# Power_Topology.net
KiCad netlist of a schematic drawn in Altium Designer
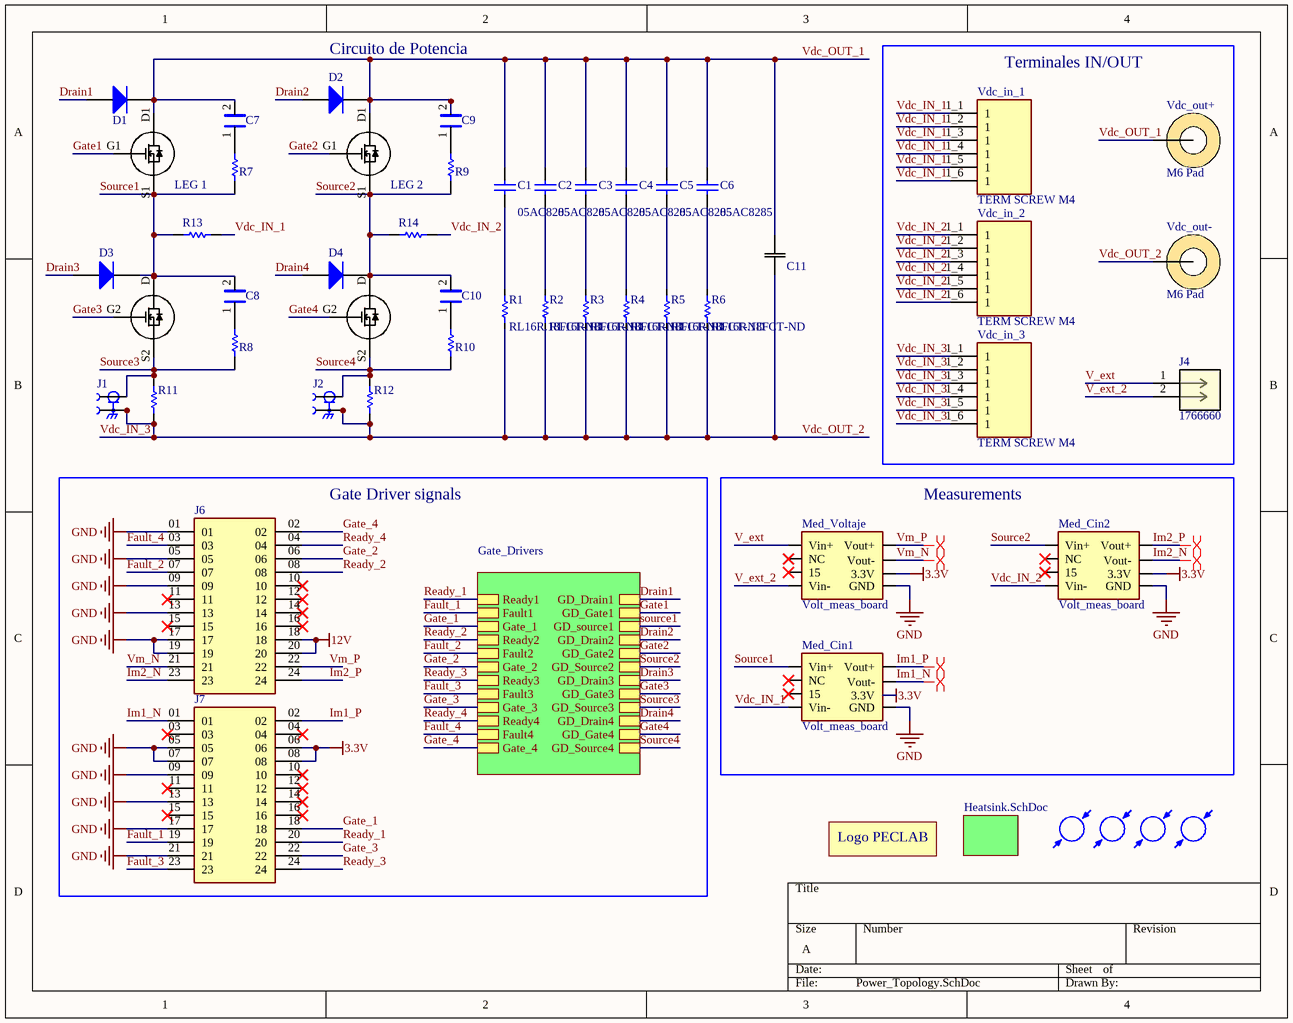
[diagram p0: Power_Topology.SchDoc]

(export (version "E")
  (design (tool "Eeschema 10.0.6"))
  (components
    (comp (ref "C1")
      (value "C1812C471JDGACTU")
      (footprint "CAP_1812")
      (description "Cap Ceramic 470pF 1000V C0G 5% SMD 1812 125°C Embossed Plastic T/R")
      (fields
        (field (name "MANUFACTURER") "KEMET")
        (field (name "TOLERANCE") "5%")
        (field (name "SUPPLIER PART NUMBER 1") "05AC8285")
      )
      (libsource (lib "H-Bridge 3-Leg - Lib") (part "C1812C471JDGACTU"))
    )
    (comp (ref "C2")
      (value "C1812C471JDGACTU")
      (footprint "CAP_1812")
      (description "Cap Ceramic 470pF 1000V C0G 5% SMD 1812 125°C Embossed Plastic T/R")
      (fields
        (field (name "MANUFACTURER") "KEMET")
        (field (name "TOLERANCE") "5%")
        (field (name "SUPPLIER PART NUMBER 1") "05AC8285")
      )
      (libsource (lib "H-Bridge 3-Leg - Lib") (part "C1812C471JDGACTU"))
    )
    (comp (ref "C3")
      (value "C1812C471JDGACTU")
      (footprint "CAP_1812")
      (description "Cap Ceramic 470pF 1000V C0G 5% SMD 1812 125°C Embossed Plastic T/R")
      (fields
        (field (name "MANUFACTURER") "KEMET")
        (field (name "TOLERANCE") "5%")
        (field (name "SUPPLIER PART NUMBER 1") "05AC8285")
      )
      (libsource (lib "H-Bridge 3-Leg - Lib") (part "C1812C471JDGACTU"))
    )
    (comp (ref "C4")
      (value "C1812C471JDGACTU")
      (footprint "CAP_1812")
      (description "Cap Ceramic 470pF 1000V C0G 5% SMD 1812 125°C Embossed Plastic T/R")
      (fields
        (field (name "MANUFACTURER") "KEMET")
        (field (name "TOLERANCE") "5%")
        (field (name "SUPPLIER PART NUMBER 1") "05AC8285")
      )
      (libsource (lib "H-Bridge 3-Leg - Lib") (part "C1812C471JDGACTU"))
    )
    (comp (ref "C5")
      (value "C1812C471JDGACTU")
      (footprint "CAP_1812")
      (description "Cap Ceramic 470pF 1000V C0G 5% SMD 1812 125°C Embossed Plastic T/R")
      (fields
        (field (name "MANUFACTURER") "KEMET")
        (field (name "TOLERANCE") "5%")
        (field (name "SUPPLIER PART NUMBER 1") "05AC8285")
      )
      (libsource (lib "H-Bridge 3-Leg - Lib") (part "C1812C471JDGACTU"))
    )
    (comp (ref "C6")
      (value "C1812C471JDGACTU")
      (footprint "CAP_1812")
      (description "Cap Ceramic 470pF 1000V C0G 5% SMD 1812 125°C Embossed Plastic T/R")
      (fields
        (field (name "MANUFACTURER") "KEMET")
        (field (name "TOLERANCE") "5%")
        (field (name "SUPPLIER PART NUMBER 1") "05AC8285")
      )
      (libsource (lib "H-Bridge 3-Leg - Lib") (part "C1812C471JDGACTU"))
    )
    (comp (ref "C7")
      (value "C1808C681JGGAC7800")
      (footprint "CAPC4520X200N")
      (description "CAP CER 680PF 2KV C0G/NP0 1808")
      (fields (field (name "MF") "KEMET"))
      (libsource (lib "H-Bridge 3-Leg - Lib") (part "CAP CER 680PF 1808"))
    )
    (comp (ref "C8")
      (value "C1808C681JGGAC7800")
      (footprint "CAPC4520X200N")
      (description "CAP CER 680PF 2KV C0G/NP0 1808")
      (fields (field (name "MF") "KEMET"))
      (libsource (lib "H-Bridge 3-Leg - Lib") (part "CAP CER 680PF 1808"))
    )
    (comp (ref "C9")
      (value "C1808C681JGGAC7800")
      (footprint "CAPC4520X200N")
      (description "CAP CER 680PF 2KV C0G/NP0 1808")
      (fields (field (name "MF") "KEMET"))
      (libsource (lib "H-Bridge 3-Leg - Lib") (part "CAP CER 680PF 1808"))
    )
    (comp (ref "C10")
      (value "C1808C681JGGAC7800")
      (footprint "CAPC4520X200N")
      (description "CAP CER 680PF 2KV C0G/NP0 1808")
      (fields (field (name "MF") "KEMET"))
      (libsource (lib "H-Bridge 3-Leg - Lib") (part "CAP CER 680PF 1808"))
    )
    (comp (ref "C11")
      (value "C4AQIBU5125A12J")
      (footprint "CAP_C4AQ_B_2_KEM")
      (description "12.5 µF Film Capacitor 800V Polypropylene (PP), Metallized Radial")
      (libsource (lib "H-Bridge 3-Leg - Lib") (part "Cap Film 12.5 uF"))
    )
    (comp (ref "D1")
      (value "ES1MTR")
      (footprint "SMA")
      (description "Diode Standard 1000 V 1A Surface Mount SMA")
      (fields (field (name "MF") "SMC Diode Solutions") (field (name "CREATED") "2021_05_16_EDuran"))
      (libsource (lib "H-Bridge 3-Leg - Lib") (part "Diode_1"))
    )
    (comp (ref "D2")
      (value "ES1MTR")
      (footprint "SMA")
      (description "Diode Standard 1000 V 1A Surface Mount SMA")
      (fields (field (name "MF") "SMC Diode Solutions") (field (name "CREATED") "2021_05_16_EDuran"))
      (libsource (lib "H-Bridge 3-Leg - Lib") (part "Diode_1"))
    )
    (comp (ref "D3")
      (value "ES1MTR")
      (footprint "SMA")
      (description "Diode Standard 1000 V 1A Surface Mount SMA")
      (fields (field (name "MF") "SMC Diode Solutions") (field (name "CREATED") "2021_05_16_EDuran"))
      (libsource (lib "H-Bridge 3-Leg - Lib") (part "Diode_1"))
    )
    (comp (ref "D4")
      (value "ES1MTR")
      (footprint "SMA")
      (description "Diode Standard 1000 V 1A Surface Mount SMA")
      (fields (field (name "MF") "SMC Diode Solutions") (field (name "CREATED") "2021_05_16_EDuran"))
      (libsource (lib "H-Bridge 3-Leg - Lib") (part "Diode_1"))
    )
    (comp (ref "J1")
      (value "CONUFL001-SMD-T")
      (footprint "LINX_CONUFL001-SMD-T")
      (description "U.FL (UMCC) Connector Jack, Male Pin 50Ohm Surface Mount Solder")
      (fields (field (name "MF") "Linx"))
      (libsource (lib "H-Bridge 3-Leg - Lib") (part "CONUFL001-SMD-T"))
    )
    (comp (ref "J2")
      (value "CONUFL001-SMD-T")
      (footprint "LINX_CONUFL001-SMD-T")
      (description "U.FL (UMCC) Connector Jack, Male Pin 50Ohm Surface Mount Solder")
      (fields (field (name "MF") "Linx"))
      (libsource (lib "H-Bridge 3-Leg - Lib") (part "CONUFL001-SMD-T"))
    )
    (comp (ref "J4")
      (value "1766660")
      (footprint "CONN_1766660")
      (description "No Description Available")
      (libsource (lib "H-Bridge 3-Leg - Lib") (part "1766660"))
    )
    (comp (ref "J6")
      (value "TSW-112-08-G-D-NA")
      (footprint "SAMTEC_TSW-112-08-G-D-NA")
      (description "Conn Unshrouded Header HDR 24 POS 2.54mm Solder RA Side Entry Thru-Hole Bulk")
      (fields (field (name "MF") "Samtec"))
      (libsource (lib "H-Bridge 3-Leg - Lib") (part "TSW-112-08-G-D-NA"))
    )
    (comp (ref "J7")
      (value "TSW-112-08-G-D-NA")
      (footprint "SAMTEC_TSW-112-08-G-D-NA")
      (description "Conn Unshrouded Header HDR 24 POS 2.54mm Solder RA Side Entry Thru-Hole Bulk")
      (fields (field (name "MF") "Samtec"))
      (libsource (lib "H-Bridge 3-Leg - Lib") (part "TSW-112-08-G-D-NA"))
    )
    (comp (ref "LEG 1")
      (value "MOSFET_SINK")
      (footprint "MOSFET-TO247_LEG_1")
      (libsource (lib "H-Bridge 3-Leg - Lib") (part "MOSFET_2_SINK_LEG_2"))
    )
    (comp (ref "LEG 2")
      (value "MOSFET_SINK")
      (footprint "MOSFET-TO247_LEG_2")
      (libsource (lib "H-Bridge 3-Leg - Lib") (part "MOSFET_2_SINK_LEG_2"))
    )
    (comp (ref "Logo")
      (value "LOGO PECLAB")
      (footprint "LOGO PECLAB 2")
      (libsource (lib "H-Bridge 3-Leg - Lib") (part "LOGO PECLAB"))
    )
    (comp (ref "Med_Cin1")
      (value "Volt_meas_board")
      (footprint "Volt_meas_board")
      (description "Tarjeta de medicion de voltaje con conector receptor 4 pos 2.54mm")
      (fields (field (name "MF") "Harwin Inc") (field (name "MP") "M20-7820446"))
      (libsource (lib "H-Bridge 3-Leg - Lib") (part "Volt_meas_board"))
    )
    (comp (ref "Med_Cin2")
      (value "Volt_meas_board")
      (footprint "Volt_meas_board")
      (description "Tarjeta de medicion de voltaje con conector receptor 4 pos 2.54mm")
      (fields (field (name "MF") "Harwin Inc") (field (name "MP") "M20-7820446"))
      (libsource (lib "H-Bridge 3-Leg - Lib") (part "Volt_meas_board"))
    )
    (comp (ref "Med_Voltaje")
      (value "Volt_meas_board")
      (footprint "Volt_meas_board")
      (description "Tarjeta de medicion de voltaje con conector receptor 4 pos 2.54mm")
      (fields (field (name "MF") "Harwin Inc") (field (name "MP") "M20-7820446"))
      (libsource (lib "H-Bridge 3-Leg - Lib") (part "Volt_meas_board"))
    )
    (comp (ref "MH1")
      (value "MH_3.4")
      (footprint "MH_3.4")
      (description "Non plated through hole")
      (libsource (lib "H-Bridge 3-Leg - Lib") (part "Mounting Hole"))
    )
    (comp (ref "MH2")
      (value "MH_3.4")
      (footprint "MH_3.4")
      (description "Non plated through hole")
      (libsource (lib "H-Bridge 3-Leg - Lib") (part "Mounting Hole"))
    )
    (comp (ref "MH3")
      (value "MH_3.4")
      (footprint "MH_3.4")
      (description "Non plated through hole")
      (libsource (lib "H-Bridge 3-Leg - Lib") (part "Mounting Hole"))
    )
    (comp (ref "MH4")
      (value "MH_3.4")
      (footprint "MH_3.4")
      (description "Non plated through hole")
      (libsource (lib "H-Bridge 3-Leg - Lib") (part "Mounting Hole"))
    )
    (comp (ref "R1")
      (value "RL1632R-R180-F")
      (footprint "R_1206")
      (description "Res Thin Film 1206 0.18 Ohm 1% 0.5W(1/2W) 0ppm/C to 100ppm/C Molded SMD Automotive T/R")
      (fields
        (field (name "MANUFACTURER") "Susumu")
        (field (name "TOLERANCE") "1%")
        (field (name "SUPPLIER PART NUMBER 1") "RL16R.18FCT-ND")
      )
      (libsource (lib "H-Bridge 3-Leg - Lib") (part "RL1632R-R180-F"))
    )
    (comp (ref "R2")
      (value "RL1632R-R180-F")
      (footprint "R_1206")
      (description "Res Thin Film 1206 0.18 Ohm 1% 0.5W(1/2W) 0ppm/C to 100ppm/C Molded SMD Automotive T/R")
      (fields
        (field (name "MANUFACTURER") "Susumu")
        (field (name "TOLERANCE") "1%")
        (field (name "SUPPLIER PART NUMBER 1") "RL16R.18FCT-ND")
      )
      (libsource (lib "H-Bridge 3-Leg - Lib") (part "RL1632R-R180-F"))
    )
    (comp (ref "R3")
      (value "RL1632R-R180-F")
      (footprint "R_1206")
      (description "Res Thin Film 1206 0.18 Ohm 1% 0.5W(1/2W) 0ppm/C to 100ppm/C Molded SMD Automotive T/R")
      (fields
        (field (name "MANUFACTURER") "Susumu")
        (field (name "TOLERANCE") "1%")
        (field (name "SUPPLIER PART NUMBER 1") "RL16R.18FCT-ND")
      )
      (libsource (lib "H-Bridge 3-Leg - Lib") (part "RL1632R-R180-F"))
    )
    (comp (ref "R4")
      (value "RL1632R-R180-F")
      (footprint "R_1206")
      (description "Res Thin Film 1206 0.18 Ohm 1% 0.5W(1/2W) 0ppm/C to 100ppm/C Molded SMD Automotive T/R")
      (fields
        (field (name "MANUFACTURER") "Susumu")
        (field (name "TOLERANCE") "1%")
        (field (name "SUPPLIER PART NUMBER 1") "RL16R.18FCT-ND")
      )
      (libsource (lib "H-Bridge 3-Leg - Lib") (part "RL1632R-R180-F"))
    )
    (comp (ref "R5")
      (value "RL1632R-R180-F")
      (footprint "R_1206")
      (description "Res Thin Film 1206 0.18 Ohm 1% 0.5W(1/2W) 0ppm/C to 100ppm/C Molded SMD Automotive T/R")
      (fields
        (field (name "MANUFACTURER") "Susumu")
        (field (name "TOLERANCE") "1%")
        (field (name "SUPPLIER PART NUMBER 1") "RL16R.18FCT-ND")
      )
      (libsource (lib "H-Bridge 3-Leg - Lib") (part "RL1632R-R180-F"))
    )
    (comp (ref "R6")
      (value "RL1632R-R180-F")
      (footprint "R_1206")
      (description "Res Thin Film 1206 0.18 Ohm 1% 0.5W(1/2W) 0ppm/C to 100ppm/C Molded SMD Automotive T/R")
      (fields
        (field (name "MANUFACTURER") "Susumu")
        (field (name "TOLERANCE") "1%")
        (field (name "SUPPLIER PART NUMBER 1") "RL16R.18FCT-ND")
      )
      (libsource (lib "H-Bridge 3-Leg - Lib") (part "RL1632R-R180-F"))
    )
    (comp (ref "R7")
      (value "Res 2010 4.7 Ohms")
      (footprint "RESC5025X70N")
      (fields (field (name "MF") "Vishay Dale") (field (name "MP") "CRCW20104R70JNEFHP"))
      (libsource (lib "H-Bridge 3-Leg - Lib") (part "Res 2010 4.7 Ohms"))
    )
    (comp (ref "R8")
      (value "Res 2010 4.7 Ohms")
      (footprint "RESC5025X70N")
      (fields (field (name "MF") "Vishay Dale") (field (name "MP") "CRCW20104R70JNEFHP"))
      (libsource (lib "H-Bridge 3-Leg - Lib") (part "Res 2010 4.7 Ohms"))
    )
    (comp (ref "R9")
      (value "Res 2010 4.7 Ohms")
      (footprint "RESC5025X70N")
      (fields (field (name "MF") "Vishay Dale") (field (name "MP") "CRCW20104R70JNEFHP"))
      (libsource (lib "H-Bridge 3-Leg - Lib") (part "Res 2010 4.7 Ohms"))
    )
    (comp (ref "R10")
      (value "Res 2010 4.7 Ohms")
      (footprint "RESC5025X70N")
      (fields (field (name "MF") "Vishay Dale") (field (name "MP") "CRCW20104R70JNEFHP"))
      (libsource (lib "H-Bridge 3-Leg - Lib") (part "Res 2010 4.7 Ohms"))
    )
    (comp (ref "R11")
      (value "WSHP2818R0100FEB")
      (footprint "RES_WSHP2818_VIS")
      (description "Current Sense Resistors - SMD 10watt .01ohm 1% AEC-Q200")
      (libsource (lib "H-Bridge 3-Leg - Lib") (part "WSHP2818R0100FEB"))
    )
    (comp (ref "R12")
      (value "WSHP2818R0100FEB")
      (footprint "RES_WSHP2818_VIS")
      (description "Current Sense Resistors - SMD 10watt .01ohm 1% AEC-Q200")
      (libsource (lib "H-Bridge 3-Leg - Lib") (part "WSHP2818R0100FEB"))
    )
    (comp (ref "R13")
      (value "WSHP2818R0100FEB")
      (footprint "RES_WSHP2818_VIS")
      (description "Current Sense Resistors - SMD 10watt .01ohm 1% AEC-Q200")
      (libsource (lib "H-Bridge 3-Leg - Lib") (part "WSHP2818R0100FEB"))
    )
    (comp (ref "R14")
      (value "WSHP2818R0100FEB")
      (footprint "RES_WSHP2818_VIS")
      (description "Current Sense Resistors - SMD 10watt .01ohm 1% AEC-Q200")
      (libsource (lib "H-Bridge 3-Leg - Lib") (part "WSHP2818R0100FEB"))
    )
    (comp (ref "Vdc_in_1")
      (value "TERM SCREW M4")
      (footprint "KEYSTONE_7799")
      (description "M4 Snap In PC Mount 30Amp-w Screw Unassembled")
      (fields (field (name "MF") "Keystone") (field (name "MP") "7799"))
      (libsource (lib "H-Bridge 3-Leg - Lib") (part "TERM SCREW M4"))
    )
    (comp (ref "Vdc_in_2")
      (value "TERM SCREW M4")
      (footprint "KEYSTONE_7799")
      (description "M4 Snap In PC Mount 30Amp-w Screw Unassembled")
      (fields (field (name "MF") "Keystone") (field (name "MP") "7799"))
      (libsource (lib "H-Bridge 3-Leg - Lib") (part "TERM SCREW M4"))
    )
    (comp (ref "Vdc_in_3")
      (value "TERM SCREW M4")
      (footprint "KEYSTONE_7799")
      (description "M4 Snap In PC Mount 30Amp-w Screw Unassembled")
      (fields (field (name "MF") "Keystone") (field (name "MP") "7799"))
      (libsource (lib "H-Bridge 3-Leg - Lib") (part "TERM SCREW M4"))
    )
    (comp (ref "Vdc_out+")
      (value "M6 Pad")
      (footprint "M6 PAD Connector")
      (description "Pad M6")
      (fields (field (name "CREATED") "2021_07_09_DArancibia"))
      (libsource (lib "H-Bridge 3-Leg - Lib") (part "Con_Pad_M6"))
    )
    (comp (ref "Vdc_out-")
      (value "M6 Pad")
      (footprint "M6 PAD Connector")
      (description "Pad M6")
      (fields (field (name "CREATED") "2021_07_09_DArancibia"))
      (libsource (lib "H-Bridge 3-Leg - Lib") (part "Con_Pad_M6"))
    )
  )
  (nets
    (net (code "1") (name "/Drain1") (class "Default")
      (node (ref "D1") (pin "A") (pinfunction "A_A") (pintype "passive"))
    )
    (net (code "2") (name "/Drain2") (class "Default")
      (node (ref "D2") (pin "A") (pinfunction "A_A") (pintype "passive"))
    )
    (net (code "3") (name "/Drain3") (class "Default")
      (node (ref "D3") (pin "A") (pinfunction "A_A") (pintype "passive"))
    )
    (net (code "4") (name "/Drain4") (class "Default")
      (node (ref "D4") (pin "A") (pinfunction "A_A") (pintype "passive"))
    )
    (net (code "5") (name "/Fault_1") (class "Default")
      (node (ref "J7") (pin "19") (pinfunction "19_19") (pintype "passive"))
    )
    (net (code "6") (name "/Fault_2") (class "Default")
      (node (ref "J6") (pin "07") (pinfunction "07_07") (pintype "passive"))
    )
    (net (code "7") (name "/Fault_3") (class "Default")
      (node (ref "J7") (pin "23") (pinfunction "23_23") (pintype "passive"))
    )
    (net (code "8") (name "/Fault_4") (class "Default")
      (node (ref "J6") (pin "03") (pinfunction "03_03") (pintype "passive"))
    )
    (net (code "9") (name "/Gate1") (class "Default")
      (node (ref "LEG 1") (pin "G1") (pinfunction "G1_G1") (pintype "passive"))
    )
    (net (code "10") (name "/Gate2") (class "Default")
      (node (ref "LEG 2") (pin "G1") (pinfunction "G1_G1") (pintype "passive"))
    )
    (net (code "11") (name "/Gate3") (class "Default")
      (node (ref "LEG 1") (pin "G2") (pinfunction "G2_G2") (pintype "passive"))
    )
    (net (code "12") (name "/Gate4") (class "Default")
      (node (ref "LEG 2") (pin "G2") (pinfunction "G2_G2") (pintype "passive"))
    )
    (net (code "13") (name "/Gate_1") (class "Default")
      (node (ref "J7") (pin "18") (pinfunction "18_18") (pintype "passive"))
    )
    (net (code "14") (name "/Gate_2") (class "Default")
      (node (ref "J6") (pin "06") (pinfunction "06_06") (pintype "passive"))
    )
    (net (code "15") (name "/Gate_3") (class "Default")
      (node (ref "J7") (pin "22") (pinfunction "22_22") (pintype "passive"))
    )
    (net (code "16") (name "/Gate_4") (class "Default")
      (node (ref "J6") (pin "02") (pinfunction "02_02") (pintype "passive"))
    )
    (net (code "17") (name "/Im1_N") (class "Default")
      (node (ref "J7") (pin "01") (pinfunction "01_01") (pintype "passive"))
      (node (ref "Med_Cin1") (pin "5") (pinfunction "Vout-_5") (pintype "passive"))
    )
    (net (code "18") (name "/Im1_P") (class "Default")
      (node (ref "J7") (pin "02") (pinfunction "02_02") (pintype "passive"))
      (node (ref "Med_Cin1") (pin "4") (pinfunction "Vout+_4") (pintype "passive"))
    )
    (net (code "19") (name "/Im2_N") (class "Default")
      (node (ref "J6") (pin "23") (pinfunction "23_23") (pintype "passive"))
      (node (ref "Med_Cin2") (pin "5") (pinfunction "Vout-_5") (pintype "passive"))
    )
    (net (code "20") (name "/Im2_P") (class "Default")
      (node (ref "J6") (pin "24") (pinfunction "24_24") (pintype "passive"))
      (node (ref "Med_Cin2") (pin "4") (pinfunction "Vout+_4") (pintype "passive"))
    )
    (net (code "21") (name "/Ready_1") (class "Default")
      (node (ref "J7") (pin "20") (pinfunction "20_20") (pintype "passive"))
    )
    (net (code "22") (name "/Ready_2") (class "Default")
      (node (ref "J6") (pin "08") (pinfunction "08_08") (pintype "passive"))
    )
    (net (code "23") (name "/Ready_3") (class "Default")
      (node (ref "J7") (pin "24") (pinfunction "24_24") (pintype "passive"))
    )
    (net (code "24") (name "/Ready_4") (class "Default")
      (node (ref "J6") (pin "04") (pinfunction "04_04") (pintype "passive"))
    )
    (net (code "25") (name "/Source1") (class "Default")
      (node (ref "C8") (pin "2") (pinfunction "2_2") (pintype "passive"))
      (node (ref "D3") (pin "K") (pinfunction "K_K") (pintype "passive"))
      (node (ref "LEG 1") (pin "D") (pinfunction "D_D") (pintype "passive"))
      (node (ref "LEG 1") (pin "S1") (pinfunction "S1_S1") (pintype "passive"))
      (node (ref "Med_Cin1") (pin "0") (pinfunction "Vin+_0") (pintype "passive"))
      (node (ref "R13") (pin "1") (pinfunction "1_1") (pintype "passive"))
      (node (ref "R7") (pin "1") (pinfunction "1_1") (pintype "passive"))
    )
    (net (code "26") (name "/Source2") (class "Default")
      (node (ref "C10") (pin "2") (pinfunction "2_2") (pintype "passive"))
      (node (ref "D4") (pin "K") (pinfunction "K_K") (pintype "passive"))
      (node (ref "LEG 2") (pin "D") (pinfunction "D_D") (pintype "passive"))
      (node (ref "LEG 2") (pin "S1") (pinfunction "S1_S1") (pintype "passive"))
      (node (ref "Med_Cin2") (pin "0") (pinfunction "Vin+_0") (pintype "passive"))
      (node (ref "R14") (pin "1") (pinfunction "1_1") (pintype "passive"))
      (node (ref "R9") (pin "1") (pinfunction "1_1") (pintype "passive"))
    )
    (net (code "27") (name "/Source3") (class "Default")
      (node (ref "J1") (pin "1") (pinfunction "1_1") (pintype "passive"))
      (node (ref "LEG 1") (pin "S2") (pinfunction "S2_S2") (pintype "passive"))
      (node (ref "R11") (pin "1") (pinfunction "1_1") (pintype "passive"))
      (node (ref "R8") (pin "1") (pinfunction "1_1") (pintype "passive"))
    )
    (net (code "28") (name "/Source4") (class "Default")
      (node (ref "J2") (pin "1") (pinfunction "1_1") (pintype "passive"))
      (node (ref "LEG 2") (pin "S2") (pinfunction "S2_S2") (pintype "passive"))
      (node (ref "R10") (pin "1") (pinfunction "1_1") (pintype "passive"))
      (node (ref "R12") (pin "1") (pinfunction "1_1") (pintype "passive"))
    )
    (net (code "29") (name "/V_ext") (class "Default")
      (node (ref "J4") (pin "1") (pinfunction "1_1") (pintype "passive"))
      (node (ref "Med_Voltaje") (pin "0") (pinfunction "Vin+_0") (pintype "passive"))
    )
    (net (code "30") (name "/V_ext_2") (class "Default")
      (node (ref "J4") (pin "2") (pinfunction "2_2") (pintype "passive"))
      (node (ref "Med_Voltaje") (pin "3") (pinfunction "Vin-_3") (pintype "passive"))
    )
    (net (code "31") (name "/Vdc_IN_1") (class "Default")
      (node (ref "Med_Cin1") (pin "3") (pinfunction "Vin-_3") (pintype "passive"))
      (node (ref "R13") (pin "2") (pinfunction "2_2") (pintype "passive"))
      (node (ref "Vdc_in_1") (pin "1_1") (pinfunction "1_1_1") (pintype "passive"))
      (node (ref "Vdc_in_1") (pin "1_2") (pinfunction "1_1_2") (pintype "passive"))
      (node (ref "Vdc_in_1") (pin "1_3") (pinfunction "1_1_3") (pintype "passive"))
      (node (ref "Vdc_in_1") (pin "1_4") (pinfunction "1_1_4") (pintype "passive"))
      (node (ref "Vdc_in_1") (pin "1_5") (pinfunction "1_1_5") (pintype "passive"))
      (node (ref "Vdc_in_1") (pin "1_6") (pinfunction "1_1_6") (pintype "passive"))
    )
    (net (code "32") (name "/Vdc_IN_2") (class "Default")
      (node (ref "Med_Cin2") (pin "3") (pinfunction "Vin-_3") (pintype "passive"))
      (node (ref "R14") (pin "2") (pinfunction "2_2") (pintype "passive"))
      (node (ref "Vdc_in_2") (pin "1_1") (pinfunction "1_1_1") (pintype "passive"))
      (node (ref "Vdc_in_2") (pin "1_2") (pinfunction "1_1_2") (pintype "passive"))
      (node (ref "Vdc_in_2") (pin "1_3") (pinfunction "1_1_3") (pintype "passive"))
      (node (ref "Vdc_in_2") (pin "1_4") (pinfunction "1_1_4") (pintype "passive"))
      (node (ref "Vdc_in_2") (pin "1_5") (pinfunction "1_1_5") (pintype "passive"))
      (node (ref "Vdc_in_2") (pin "1_6") (pinfunction "1_1_6") (pintype "passive"))
    )
    (net (code "33") (name "/Vdc_IN_3") (class "Default")
      (node (ref "C11") (pin "1") (pinfunction "1_1") (pintype "passive"))
      (node (ref "J1") (pin "2") (pinfunction "2_2") (pintype "passive"))
      (node (ref "J1") (pin "3") (pinfunction "2_3") (pintype "passive"))
      (node (ref "J2") (pin "2") (pinfunction "2_2") (pintype "passive"))
      (node (ref "J2") (pin "3") (pinfunction "2_3") (pintype "passive"))
      (node (ref "R1") (pin "1") (pinfunction "1_1") (pintype "passive"))
      (node (ref "R11") (pin "2") (pinfunction "2_2") (pintype "passive"))
      (node (ref "R12") (pin "2") (pinfunction "2_2") (pintype "passive"))
      (node (ref "R2") (pin "1") (pinfunction "1_1") (pintype "passive"))
      (node (ref "R3") (pin "1") (pinfunction "1_1") (pintype "passive"))
      (node (ref "R4") (pin "1") (pinfunction "1_1") (pintype "passive"))
      (node (ref "R5") (pin "1") (pinfunction "1_1") (pintype "passive"))
      (node (ref "R6") (pin "1") (pinfunction "1_1") (pintype "passive"))
      (node (ref "Vdc_in_3") (pin "1_1") (pinfunction "1_1_1") (pintype "passive"))
      (node (ref "Vdc_in_3") (pin "1_2") (pinfunction "1_1_2") (pintype "passive"))
      (node (ref "Vdc_in_3") (pin "1_3") (pinfunction "1_1_3") (pintype "passive"))
      (node (ref "Vdc_in_3") (pin "1_4") (pinfunction "1_1_4") (pintype "passive"))
      (node (ref "Vdc_in_3") (pin "1_5") (pinfunction "1_1_5") (pintype "passive"))
      (node (ref "Vdc_in_3") (pin "1_6") (pinfunction "1_1_6") (pintype "passive"))
      (node (ref "Vdc_out-") (pin "1") (pinfunction "1_1") (pintype "passive"))
    )
    (net (code "34") (name "/Vdc_OUT_1") (class "Default")
      (node (ref "C1") (pin "1") (pinfunction "1_1") (pintype "passive"))
      (node (ref "C11") (pin "2") (pinfunction "2_2") (pintype "passive"))
      (node (ref "C2") (pin "1") (pinfunction "1_1") (pintype "passive"))
      (node (ref "C3") (pin "1") (pinfunction "1_1") (pintype "passive"))
      (node (ref "C4") (pin "1") (pinfunction "1_1") (pintype "passive"))
      (node (ref "C5") (pin "1") (pinfunction "1_1") (pintype "passive"))
      (node (ref "C6") (pin "1") (pinfunction "1_1") (pintype "passive"))
      (node (ref "C7") (pin "2") (pinfunction "2_2") (pintype "passive"))
      (node (ref "C9") (pin "2") (pinfunction "2_2") (pintype "passive"))
      (node (ref "D1") (pin "K") (pinfunction "K_K") (pintype "passive"))
      (node (ref "D2") (pin "K") (pinfunction "K_K") (pintype "passive"))
      (node (ref "LEG 1") (pin "D1") (pinfunction "D1_D1") (pintype "passive"))
      (node (ref "LEG 2") (pin "D1") (pinfunction "D1_D1") (pintype "passive"))
      (node (ref "Vdc_out+") (pin "1") (pinfunction "1_1") (pintype "passive"))
    )
    (net (code "35") (name "/Vm_N") (class "Default")
      (node (ref "J6") (pin "21") (pinfunction "21_21") (pintype "passive"))
      (node (ref "Med_Voltaje") (pin "5") (pinfunction "Vout-_5") (pintype "passive"))
    )
    (net (code "36") (name "/Vm_P") (class "Default")
      (node (ref "J6") (pin "22") (pinfunction "22_22") (pintype "passive"))
      (node (ref "Med_Voltaje") (pin "4") (pinfunction "Vout+_4") (pintype "passive"))
    )
    (net (code "38") (name "3.3V") (class "Default")
      (node (ref "J7") (pin "06") (pinfunction "06_06") (pintype "passive"))
      (node (ref "J7") (pin "08") (pinfunction "08_08") (pintype "passive"))
      (node (ref "Med_Cin1") (pin "6") (pinfunction "3.3V_6") (pintype "passive"))
      (node (ref "Med_Cin2") (pin "6") (pinfunction "3.3V_6") (pintype "passive"))
      (node (ref "Med_Voltaje") (pin "6") (pinfunction "3.3V_6") (pintype "passive"))
    )
    (net (code "39") (name "12V") (class "Default")
      (node (ref "J6") (pin "18") (pinfunction "18_18") (pintype "passive"))
      (node (ref "J6") (pin "20") (pinfunction "20_20") (pintype "passive"))
    )
    (net (code "40") (name "GND") (class "Default")
      (node (ref "J6") (pin "01") (pinfunction "01_01") (pintype "passive"))
      (node (ref "J6") (pin "05") (pinfunction "05_05") (pintype "passive"))
      (node (ref "J6") (pin "09") (pinfunction "09_09") (pintype "passive"))
      (node (ref "J6") (pin "13") (pinfunction "13_13") (pintype "passive"))
      (node (ref "J6") (pin "17") (pinfunction "17_17") (pintype "passive"))
      (node (ref "J6") (pin "19") (pinfunction "19_19") (pintype "passive"))
      (node (ref "J7") (pin "05") (pinfunction "05_05") (pintype "passive"))
      (node (ref "J7") (pin "07") (pinfunction "07_07") (pintype "passive"))
      (node (ref "J7") (pin "09") (pinfunction "09_09") (pintype "passive"))
      (node (ref "J7") (pin "13") (pinfunction "13_13") (pintype "passive"))
      (node (ref "J7") (pin "17") (pinfunction "17_17") (pintype "passive"))
      (node (ref "J7") (pin "21") (pinfunction "21_21") (pintype "passive"))
      (node (ref "Med_Cin1") (pin "7") (pinfunction "GND_7") (pintype "passive"))
      (node (ref "Med_Cin2") (pin "7") (pinfunction "GND_7") (pintype "passive"))
      (node (ref "Med_Voltaje") (pin "7") (pinfunction "GND_7") (pintype "passive"))
    )
    (net (code "41") (name "Net-(C1-Pad2)") (class "Default")
      (node (ref "C1") (pin "2") (pinfunction "2_2") (pintype "passive"))
      (node (ref "R1") (pin "2") (pinfunction "2_2") (pintype "passive"))
    )
    (net (code "42") (name "Net-(C2-Pad2)") (class "Default")
      (node (ref "C2") (pin "2") (pinfunction "2_2") (pintype "passive"))
      (node (ref "R2") (pin "2") (pinfunction "2_2") (pintype "passive"))
    )
    (net (code "43") (name "Net-(C3-Pad2)") (class "Default")
      (node (ref "C3") (pin "2") (pinfunction "2_2") (pintype "passive"))
      (node (ref "R3") (pin "2") (pinfunction "2_2") (pintype "passive"))
    )
    (net (code "44") (name "Net-(C4-Pad2)") (class "Default")
      (node (ref "C4") (pin "2") (pinfunction "2_2") (pintype "passive"))
      (node (ref "R4") (pin "2") (pinfunction "2_2") (pintype "passive"))
    )
    (net (code "45") (name "Net-(C5-Pad2)") (class "Default")
      (node (ref "C5") (pin "2") (pinfunction "2_2") (pintype "passive"))
      (node (ref "R5") (pin "2") (pinfunction "2_2") (pintype "passive"))
    )
    (net (code "46") (name "Net-(C6-Pad2)") (class "Default")
      (node (ref "C6") (pin "2") (pinfunction "2_2") (pintype "passive"))
      (node (ref "R6") (pin "2") (pinfunction "2_2") (pintype "passive"))
    )
    (net (code "47") (name "Net-(C7-Pad1)") (class "Default")
      (node (ref "C7") (pin "1") (pinfunction "1_1") (pintype "passive"))
      (node (ref "R7") (pin "2") (pinfunction "2_2") (pintype "passive"))
    )
    (net (code "48") (name "Net-(C8-Pad1)") (class "Default")
      (node (ref "C8") (pin "1") (pinfunction "1_1") (pintype "passive"))
      (node (ref "R8") (pin "2") (pinfunction "2_2") (pintype "passive"))
    )
    (net (code "49") (name "Net-(C9-Pad1)") (class "Default")
      (node (ref "C9") (pin "1") (pinfunction "1_1") (pintype "passive"))
      (node (ref "R9") (pin "2") (pinfunction "2_2") (pintype "passive"))
    )
    (net (code "50") (name "Net-(C10-Pad1)") (class "Default")
      (node (ref "C10") (pin "1") (pinfunction "1_1") (pintype "passive"))
      (node (ref "R10") (pin "2") (pinfunction "2_2") (pintype "passive"))
    )
    (net (code "51") (name "unconnected-(J6-Pad10)") (class "Default")
      (node (ref "J6") (pin "10") (pinfunction "10_10") (pintype "passive+no_connect"))
    )
    (net (code "52") (name "unconnected-(J6-Pad11)") (class "Default")
      (node (ref "J6") (pin "11") (pinfunction "11_11") (pintype "passive+no_connect"))
    )
    (net (code "53") (name "unconnected-(J6-Pad12)") (class "Default")
      (node (ref "J6") (pin "12") (pinfunction "12_12") (pintype "passive+no_connect"))
    )
    (net (code "54") (name "unconnected-(J6-Pad14)") (class "Default")
      (node (ref "J6") (pin "14") (pinfunction "14_14") (pintype "passive+no_connect"))
    )
    (net (code "55") (name "unconnected-(J6-Pad15)") (class "Default")
      (node (ref "J6") (pin "15") (pinfunction "15_15") (pintype "passive+no_connect"))
    )
    (net (code "56") (name "unconnected-(J6-Pad16)") (class "Default")
      (node (ref "J6") (pin "16") (pinfunction "16_16") (pintype "passive+no_connect"))
    )
    (net (code "57") (name "unconnected-(J7-Pad03)") (class "Default")
      (node (ref "J7") (pin "03") (pinfunction "03_03") (pintype "passive+no_connect"))
    )
    (net (code "58") (name "unconnected-(J7-Pad04)") (class "Default")
      (node (ref "J7") (pin "04") (pinfunction "04_04") (pintype "passive+no_connect"))
    )
    (net (code "59") (name "unconnected-(J7-Pad10)") (class "Default")
      (node (ref "J7") (pin "10") (pinfunction "10_10") (pintype "passive+no_connect"))
    )
    (net (code "60") (name "unconnected-(J7-Pad11)") (class "Default")
      (node (ref "J7") (pin "11") (pinfunction "11_11") (pintype "passive+no_connect"))
    )
    (net (code "61") (name "unconnected-(J7-Pad12)") (class "Default")
      (node (ref "J7") (pin "12") (pinfunction "12_12") (pintype "passive+no_connect"))
    )
    (net (code "62") (name "unconnected-(J7-Pad14)") (class "Default")
      (node (ref "J7") (pin "14") (pinfunction "14_14") (pintype "passive+no_connect"))
    )
    (net (code "63") (name "unconnected-(J7-Pad15)") (class "Default")
      (node (ref "J7") (pin "15") (pinfunction "15_15") (pintype "passive+no_connect"))
    )
    (net (code "64") (name "unconnected-(J7-Pad16)") (class "Default")
      (node (ref "J7") (pin "16") (pinfunction "16_16") (pintype "passive+no_connect"))
    )
    (net (code "65") (name "unconnected-(Med_Cin1-15-Pad2)") (class "Default")
      (node (ref "Med_Cin1") (pin "2") (pinfunction "15_2") (pintype "passive+no_connect"))
    )
    (net (code "66") (name "unconnected-(Med_Cin1-NC-Pad1)") (class "Default")
      (node (ref "Med_Cin1") (pin "1") (pinfunction "NC_1") (pintype "passive+no_connect"))
    )
    (net (code "67") (name "unconnected-(Med_Cin2-15-Pad2)") (class "Default")
      (node (ref "Med_Cin2") (pin "2") (pinfunction "15_2") (pintype "passive+no_connect"))
    )
    (net (code "68") (name "unconnected-(Med_Cin2-NC-Pad1)") (class "Default")
      (node (ref "Med_Cin2") (pin "1") (pinfunction "NC_1") (pintype "passive+no_connect"))
    )
    (net (code "69") (name "unconnected-(Med_Voltaje-15-Pad2)") (class "Default")
      (node (ref "Med_Voltaje") (pin "2") (pinfunction "15_2") (pintype "passive+no_connect"))
    )
    (net (code "70") (name "unconnected-(Med_Voltaje-NC-Pad1)") (class "Default")
      (node (ref "Med_Voltaje") (pin "1") (pinfunction "NC_1") (pintype "passive+no_connect"))
    )
  )
)
